# draftBoard.net
KiCad netlist of a schematic drawn in EAGLE
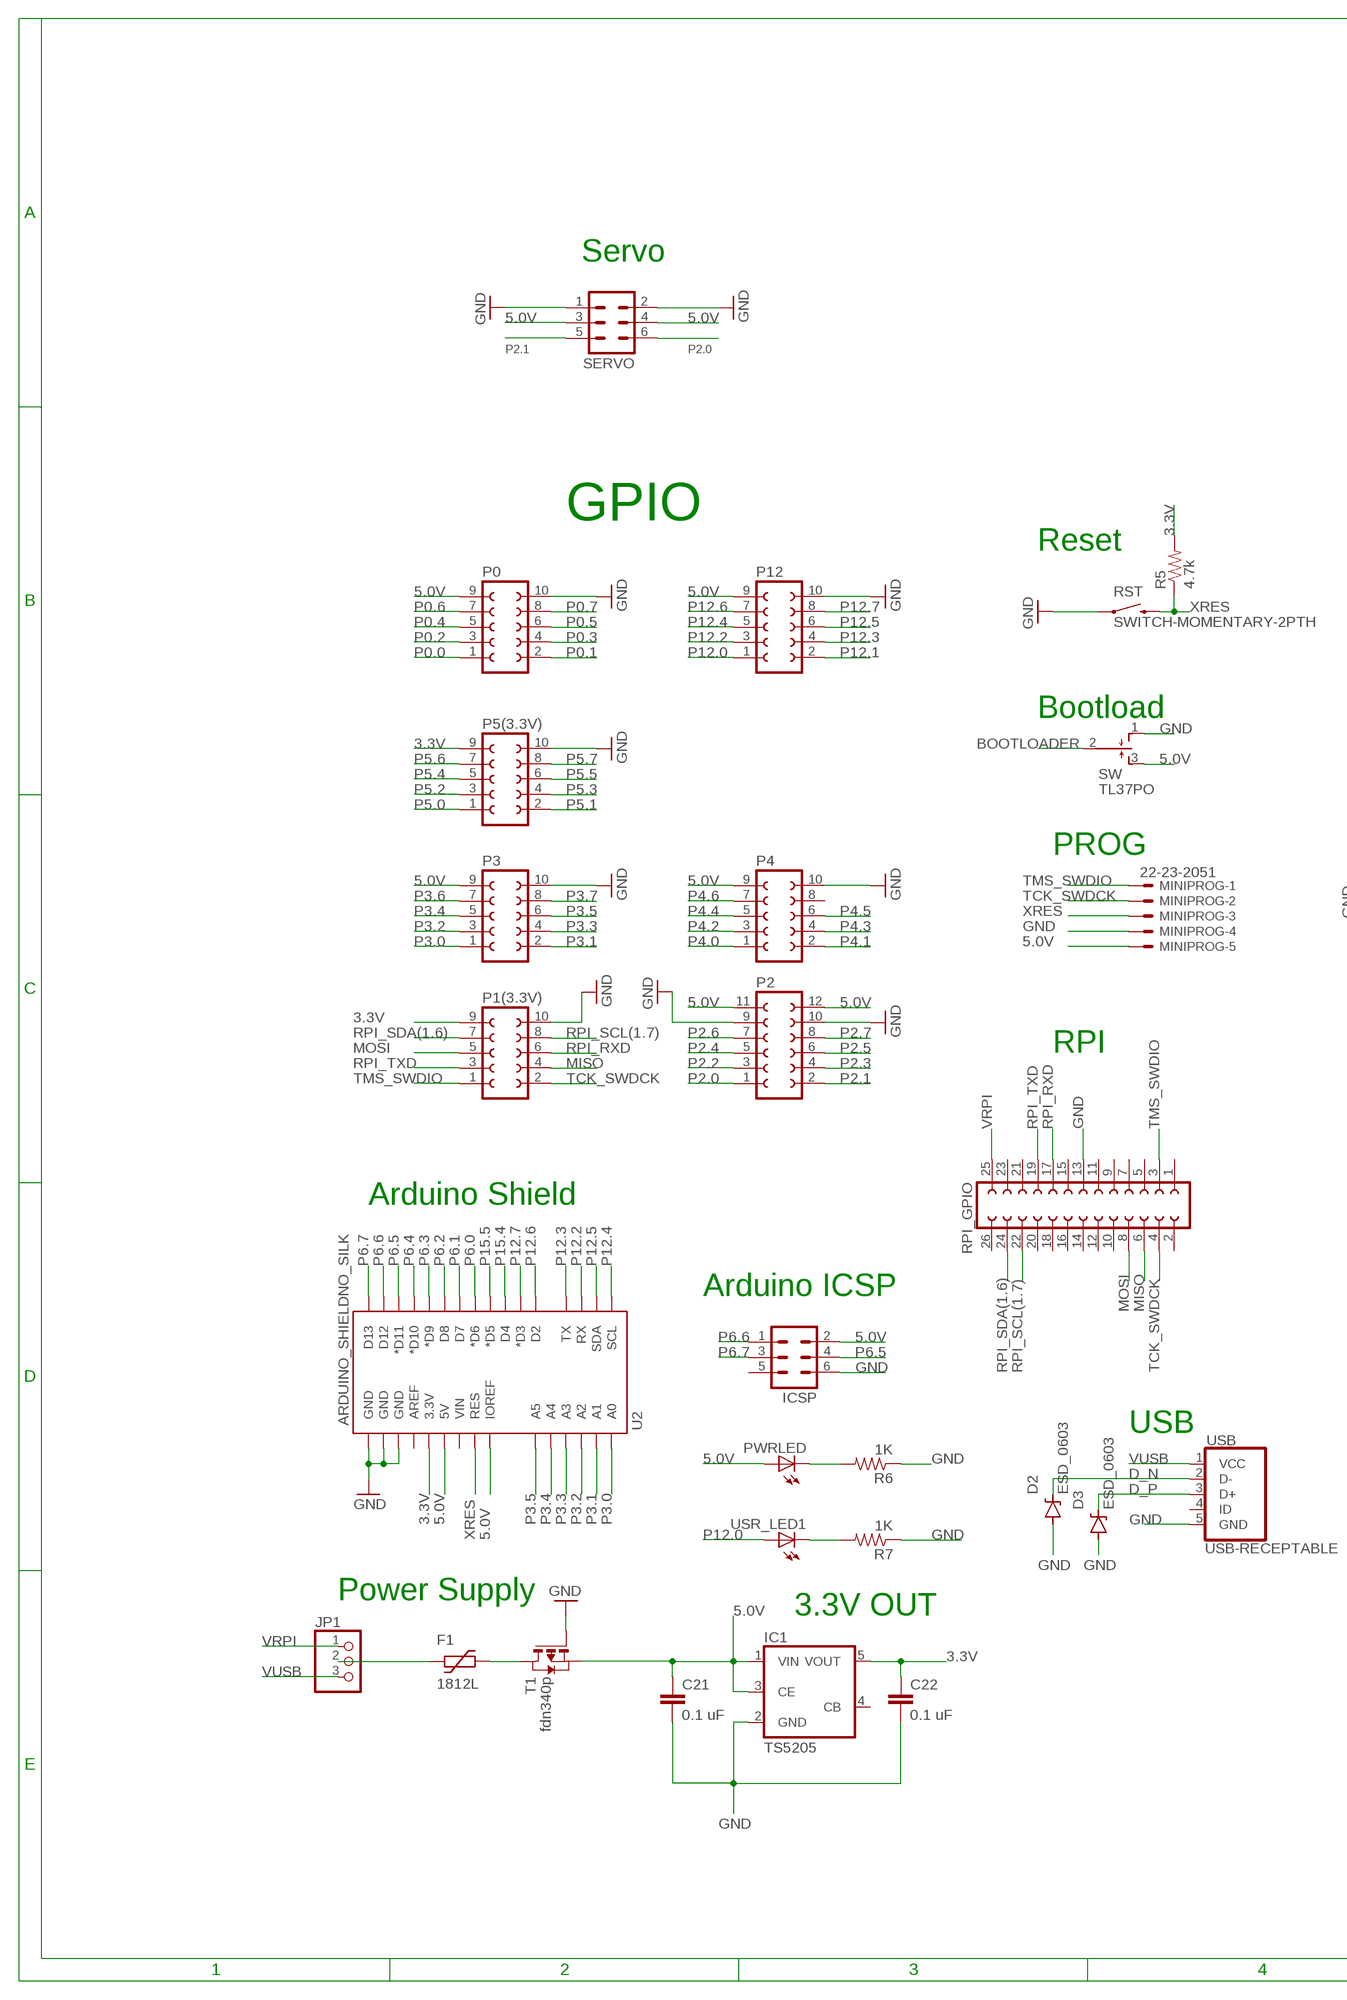
[diagram p0: schematic, sheet 1, part 1 of 2]
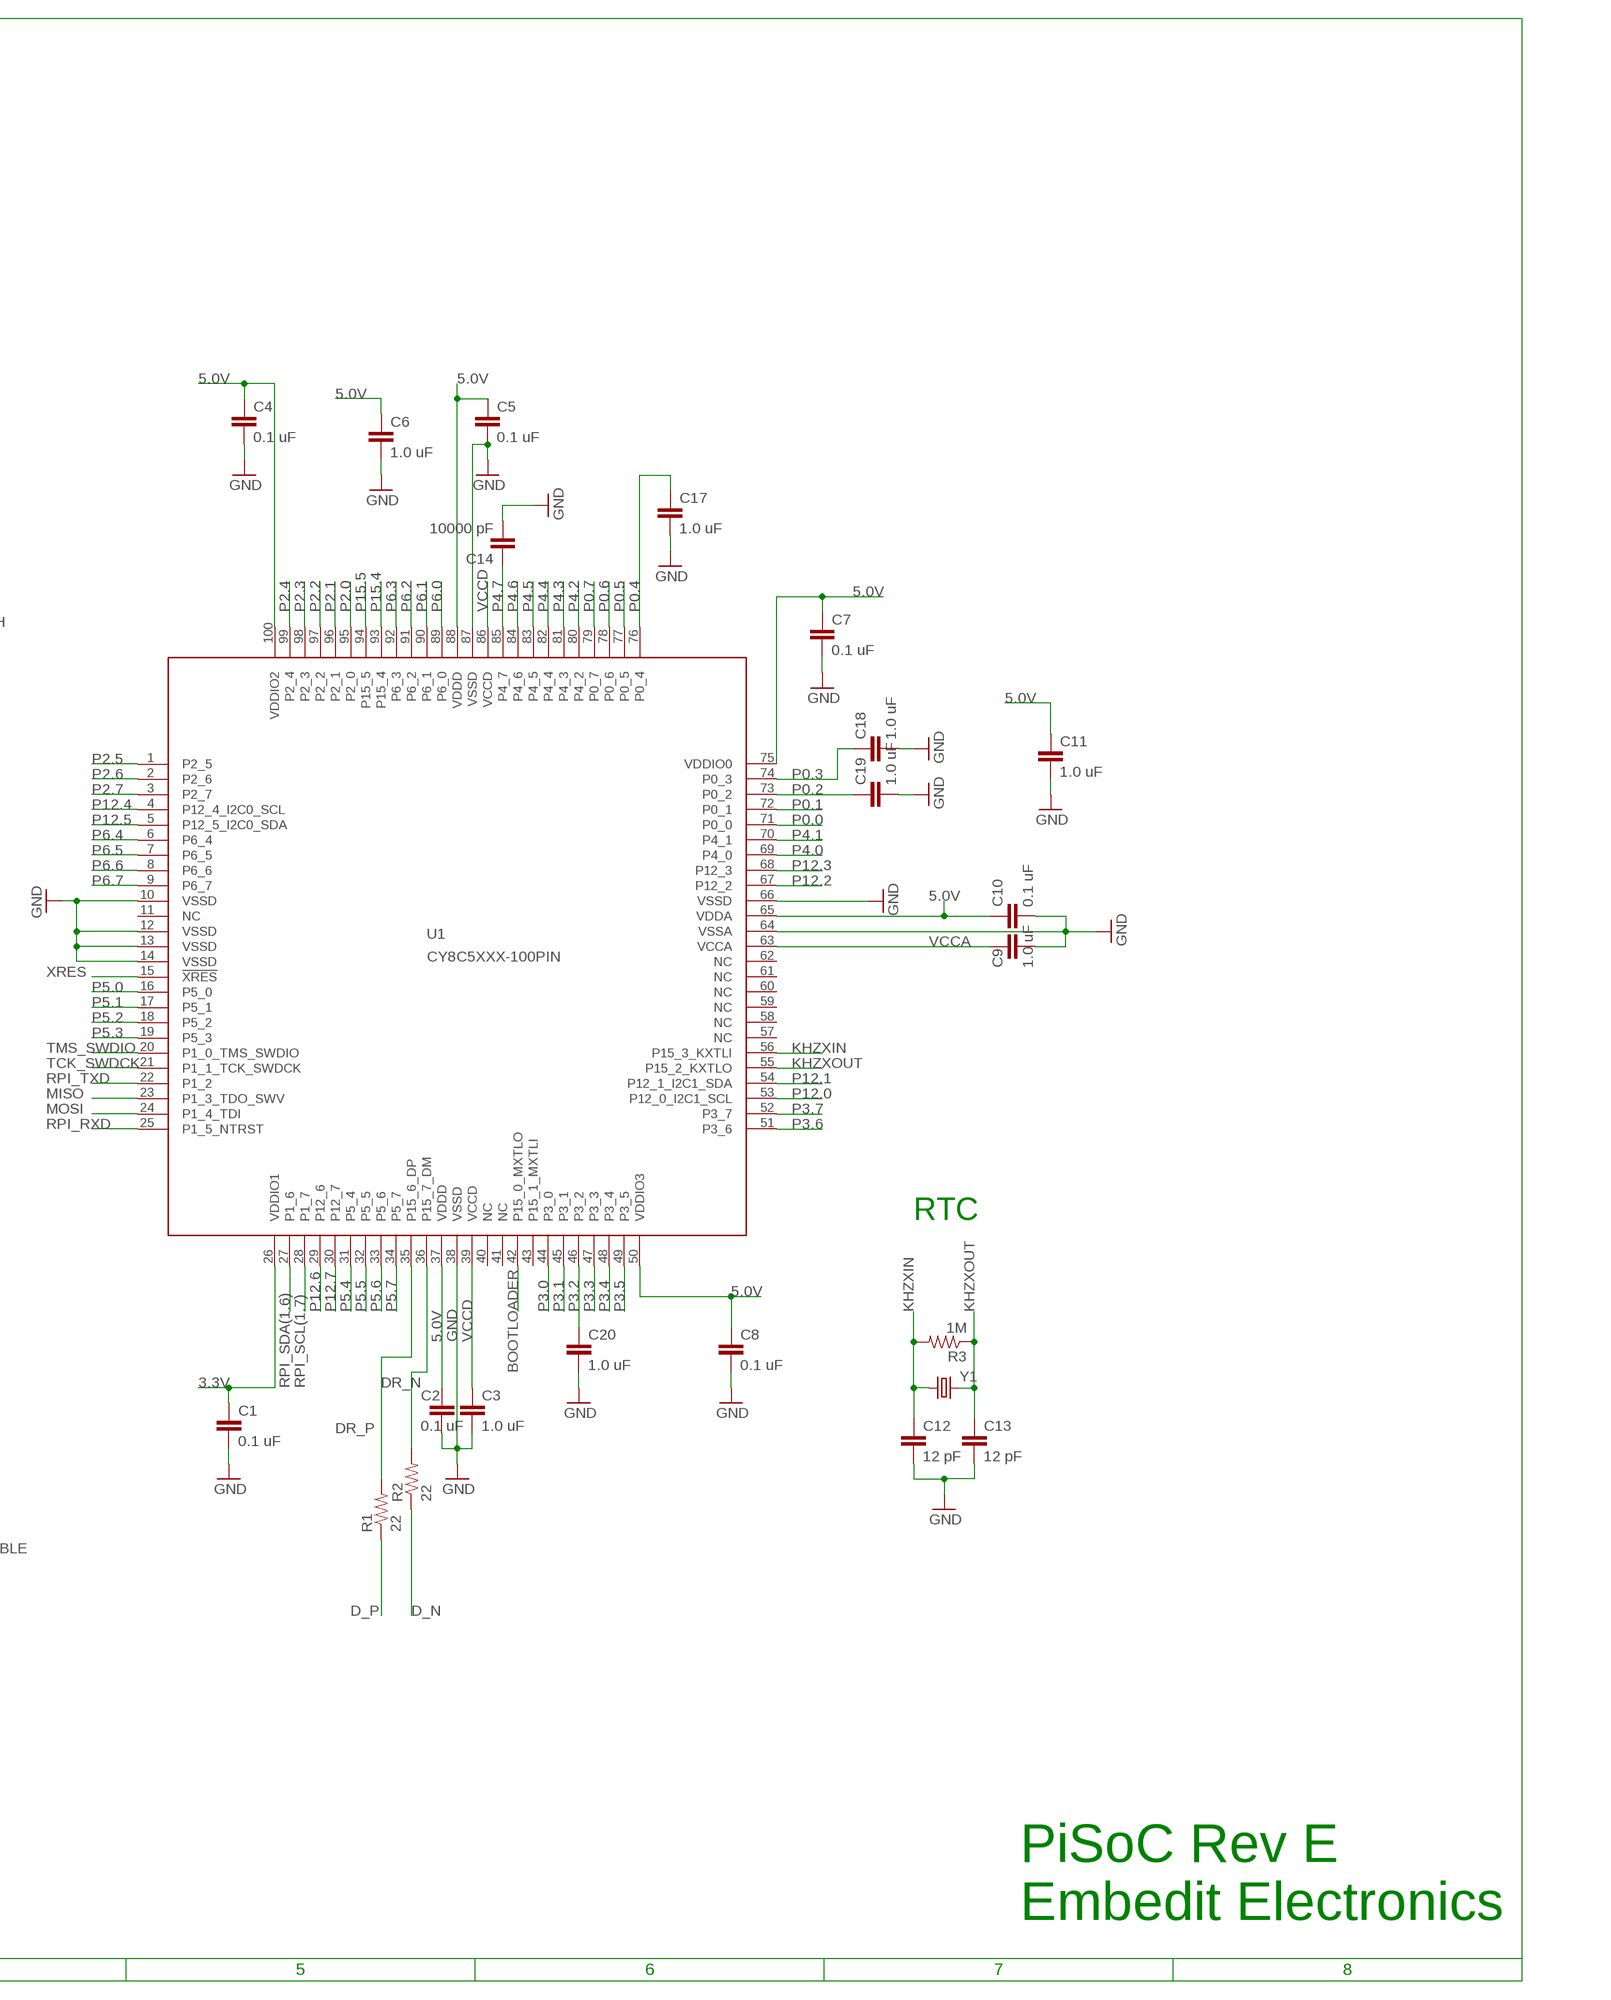
[diagram p1: schematic, sheet 1, part 2 of 2]

(export (version "E")
  (design (tool "Eeschema 10.0.6"))
  (components
    (comp (ref "C1")
      (value "0.1 uF")
      (footprint "eagle-import:0603-CAP@1")
      (libsource (lib "eagle-import") (part "CAP0603-CAP"))
    )
    (comp (ref "C2")
      (value "0.1 uF")
      (footprint "eagle-import:0603-CAP@1")
      (libsource (lib "eagle-import") (part "CAP0603-CAP"))
    )
    (comp (ref "C3")
      (value "1.0 uF")
      (footprint "eagle-import:0603-CAP@1")
      (libsource (lib "eagle-import") (part "CAP0603-CAP"))
    )
    (comp (ref "C4")
      (value "0.1 uF")
      (footprint "eagle-import:0603-CAP@1")
      (libsource (lib "eagle-import") (part "CAP0603-CAP"))
    )
    (comp (ref "C5")
      (value "0.1 uF")
      (footprint "eagle-import:0603-CAP@1")
      (libsource (lib "eagle-import") (part "CAP0603-CAP"))
    )
    (comp (ref "C6")
      (value "1.0 uF")
      (footprint "eagle-import:0603-CAP@1")
      (libsource (lib "eagle-import") (part "CAP0603-CAP"))
    )
    (comp (ref "C7")
      (value "0.1 uF")
      (footprint "eagle-import:0603-CAP@1")
      (libsource (lib "eagle-import") (part "CAP0603-CAP"))
    )
    (comp (ref "C8")
      (value "0.1 uF")
      (footprint "eagle-import:0603-CAP@1")
      (libsource (lib "eagle-import") (part "CAP0603-CAP"))
    )
    (comp (ref "C9")
      (value "1.0 uF")
      (footprint "eagle-import:0603-CAP@1")
      (libsource (lib "eagle-import") (part "CAP0603-CAP"))
    )
    (comp (ref "C10")
      (value "0.1 uF")
      (footprint "eagle-import:0603-CAP@1")
      (libsource (lib "eagle-import") (part "CAP0603-CAP"))
    )
    (comp (ref "C11")
      (value "1.0 uF")
      (footprint "eagle-import:0603-CAP@1")
      (libsource (lib "eagle-import") (part "CAP0603-CAP"))
    )
    (comp (ref "C12")
      (value "12 pF")
      (footprint "eagle-import:0603-CAP@1")
      (libsource (lib "eagle-import") (part "CAP0603-CAP"))
    )
    (comp (ref "C13")
      (value "12 pF")
      (footprint "eagle-import:0603-CAP@1")
      (libsource (lib "eagle-import") (part "CAP0603-CAP"))
    )
    (comp (ref "C14")
      (value "10000 pF")
      (footprint "eagle-import:0603-CAP@1")
      (libsource (lib "eagle-import") (part "CAP0603-CAP"))
    )
    (comp (ref "C17")
      (value "1.0 uF")
      (footprint "eagle-import:0603-CAP@1")
      (libsource (lib "eagle-import") (part "CAP0603-CAP"))
    )
    (comp (ref "C18")
      (value "1.0 uF")
      (footprint "eagle-import:0603-CAP@1")
      (libsource (lib "eagle-import") (part "CAP0603-CAP"))
    )
    (comp (ref "C19")
      (value "1.0 uF")
      (footprint "eagle-import:0603-CAP@1")
      (libsource (lib "eagle-import") (part "CAP0603-CAP"))
    )
    (comp (ref "C20")
      (value "1.0 uF")
      (footprint "eagle-import:0603-CAP@1")
      (libsource (lib "eagle-import") (part "CAP0603-CAP"))
    )
    (comp (ref "C21")
      (value "0.1 uF")
      (footprint "eagle-import:0603-CAP@1")
      (libsource (lib "eagle-import") (part "CAP0603-CAP"))
    )
    (comp (ref "C22")
      (value "0.1 uF")
      (footprint "eagle-import:0603-CAP@1")
      (libsource (lib "eagle-import") (part "CAP0603-CAP"))
    )
    (comp (ref "D2")
      (value "ESD_0603")
      (footprint "eagle-import:0603-CAP")
      (libsource (lib "eagle-import") (part "ESD_0603"))
    )
    (comp (ref "D3")
      (value "ESD_0603")
      (footprint "eagle-import:0603-CAP")
      (libsource (lib "eagle-import") (part "ESD_0603"))
    )
    (comp (ref "F1")
      (value "1812L")
      (footprint "eagle-import:1812L")
      (libsource (lib "eagle-import") (part "1812L"))
    )
    (comp (ref "IC1")
      (value "TS5205")
      (footprint "eagle-import:SOT25")
      (libsource (lib "eagle-import") (part "TS5205"))
    )
    (comp (ref "ICSP")
      (value "MA03-2")
      (footprint "eagle-import:MA03-2")
      (libsource (lib "eagle-import") (part "MA03-2"))
    )
    (comp (ref "JP1")
      (value "PINHD-1X3")
      (footprint "eagle-import:1X03")
      (libsource (lib "eagle-import") (part "PINHD-1X3"))
    )
    (comp (ref "MINIPROG")
      (value "22-23-2051")
      (footprint "eagle-import:22-23-2051")
      (fields (field (name "MF") "MOLEX"))
      (libsource (lib "eagle-import") (part "22-23-2051"))
    )
    (comp (ref "P0")
      (value "FE05-2")
      (footprint "eagle-import:FE05-2")
      (libsource (lib "eagle-import") (part "FE05-2"))
    )
    (comp (ref "P1(3.3V)")
      (value "FE05-2")
      (footprint "eagle-import:FE05-2")
      (libsource (lib "eagle-import") (part "FE05-2"))
    )
    (comp (ref "P2")
      (value "FE06-2")
      (footprint "eagle-import:FE06-2")
      (libsource (lib "eagle-import") (part "FE06-2"))
    )
    (comp (ref "P3")
      (value "FE05-2")
      (footprint "eagle-import:FE05-2")
      (libsource (lib "eagle-import") (part "FE05-2"))
    )
    (comp (ref "P4")
      (value "FE05-2")
      (footprint "eagle-import:FE05-2")
      (libsource (lib "eagle-import") (part "FE05-2"))
    )
    (comp (ref "P5(3.3V)")
      (value "FE05-2")
      (footprint "eagle-import:FE05-2")
      (libsource (lib "eagle-import") (part "FE05-2"))
    )
    (comp (ref "P12")
      (value "FE05-2")
      (footprint "eagle-import:FE05-2")
      (libsource (lib "eagle-import") (part "FE05-2"))
    )
    (comp (ref "PWRLED")
      (value "LED0603")
      (footprint "eagle-import:LED-0603")
      (libsource (lib "eagle-import") (part "LED0603"))
    )
    (comp (ref "R1")
      (value "22")
      (footprint "eagle-import:0603-RES")
      (libsource (lib "eagle-import") (part "RESISTOR0603-RES"))
    )
    (comp (ref "R2")
      (value "22")
      (footprint "eagle-import:0603-RES")
      (libsource (lib "eagle-import") (part "RESISTOR0603-RES"))
    )
    (comp (ref "R3")
      (value "1M")
      (footprint "eagle-import:0603-RES")
      (libsource (lib "eagle-import") (part "RESISTOR0603-RES"))
    )
    (comp (ref "R5")
      (value "4.7k")
      (footprint "eagle-import:0603-RES")
      (libsource (lib "eagle-import") (part "RESISTOR0603-RES"))
    )
    (comp (ref "R6")
      (value "1K")
      (footprint "eagle-import:0603-RES")
      (libsource (lib "eagle-import") (part "RESISTOR0603-RES"))
    )
    (comp (ref "R7")
      (value "1K")
      (footprint "eagle-import:0603-RES")
      (libsource (lib "eagle-import") (part "RESISTOR0603-RES"))
    )
    (comp (ref "RPI_GPIO")
      (value "FE13-2")
      (footprint "eagle-import:FE13-2")
      (libsource (lib "eagle-import") (part "FE13-2"))
    )
    (comp (ref "RST")
      (value "SWITCH-MOMENTARY-2PTH")
      (footprint "eagle-import:TACTILE-PTH")
      (libsource (lib "eagle-import") (part "SWITCH-MOMENTARY-2PTH"))
    )
    (comp (ref "SERVO")
      (value "MA03-2")
      (footprint "eagle-import:MA03-2")
      (libsource (lib "eagle-import") (part "MA03-2"))
    )
    (comp (ref "SW")
      (value "TL37PO")
      (footprint "eagle-import:TL3XPO")
      (libsource (lib "eagle-import") (part "TL37PO"))
    )
    (comp (ref "T1")
      (value "fdn340p")
      (footprint "eagle-import:SOT-23")
      (libsource (lib "eagle-import") (part "PMOSSOT23"))
    )
    (comp (ref "U1")
      (value "CY8C5XXX-100PIN")
      (footprint "eagle-import:TQFP-14X14-100")
      (fields (field (name "MPN") "CY8C5588AXI-060"))
      (libsource (lib "eagle-import") (part "CY8C5XXX-100PIN"))
    )
    (comp (ref "U2")
      (value "ARDUINO_SHIELDNO_SILK")
      (footprint "eagle-import:DUEMILANOVE_VIAS")
      (libsource (lib "eagle-import") (part "ARDUINO_SHIELDNO_SILK"))
    )
    (comp (ref "USB")
      (value "USB-RECEPTABLE")
      (footprint "eagle-import:FCI-10103594-0001LF")
      (libsource (lib "eagle-import") (part "USB-RECEPTABLE"))
    )
    (comp (ref "USR_LED1")
      (value "LED0603")
      (footprint "eagle-import:LED-0603")
      (libsource (lib "eagle-import") (part "LED0603"))
    )
    (comp (ref "Y1")
      (value "CRYSTALTC26H")
      (footprint "eagle-import:TC26H")
      (libsource (lib "eagle-import") (part "CRYSTALTC26H"))
    )
  )
  (nets
    (net (code "1") (name "/3.3V") (class "Default")
      (node (ref "C1") (pin "1") (pinfunction "1_1") (pintype "passive"))
      (node (ref "C22") (pin "1") (pinfunction "1_1") (pintype "passive"))
      (node (ref "IC1") (pin "5") (pinfunction "VOUT_5") (pintype "passive"))
      (node (ref "P1(3.3V)") (pin "9") (pinfunction "9_9") (pintype "passive"))
      (node (ref "P5(3.3V)") (pin "9") (pinfunction "9_9") (pintype "passive"))
      (node (ref "R5") (pin "2") (pinfunction "2_2") (pintype "passive"))
      (node (ref "U1") (pin "26") (pinfunction "VDDIO1_26") (pintype "passive"))
      (node (ref "U2") (pin "3.3V") (pinfunction "3.3V_3.3V") (pintype "bidirectional"))
    )
    (net (code "2") (name "/5.0V") (class "Default")
      (node (ref "C10") (pin "1") (pinfunction "1_1") (pintype "passive"))
      (node (ref "C11") (pin "1") (pinfunction "1_1") (pintype "passive"))
      (node (ref "C2") (pin "1") (pinfunction "1_1") (pintype "passive"))
      (node (ref "C21") (pin "1") (pinfunction "1_1") (pintype "passive"))
      (node (ref "C4") (pin "1") (pinfunction "1_1") (pintype "passive"))
      (node (ref "C5") (pin "1") (pinfunction "1_1") (pintype "passive"))
      (node (ref "C6") (pin "1") (pinfunction "1_1") (pintype "passive"))
      (node (ref "C7") (pin "1") (pinfunction "1_1") (pintype "passive"))
      (node (ref "C8") (pin "1") (pinfunction "1_1") (pintype "passive"))
      (node (ref "IC1") (pin "1") (pinfunction "VIN_1") (pintype "input"))
      (node (ref "IC1") (pin "3") (pinfunction "CE_3") (pintype "input"))
      (node (ref "ICSP") (pin "2") (pinfunction "2_2") (pintype "passive"))
      (node (ref "MINIPROG") (pin "5") (pinfunction "S_5") (pintype "passive"))
      (node (ref "P0") (pin "9") (pinfunction "9_9") (pintype "passive"))
      (node (ref "P12") (pin "9") (pinfunction "9_9") (pintype "passive"))
      (node (ref "P2") (pin "11") (pinfunction "11_11") (pintype "passive"))
      (node (ref "P2") (pin "12") (pinfunction "12_12") (pintype "passive"))
      (node (ref "P3") (pin "9") (pinfunction "9_9") (pintype "passive"))
      (node (ref "P4") (pin "9") (pinfunction "9_9") (pintype "passive"))
      (node (ref "PWRLED") (pin "A") (pinfunction "A_A") (pintype "passive"))
      (node (ref "SERVO") (pin "3") (pinfunction "3_3") (pintype "passive"))
      (node (ref "SERVO") (pin "4") (pinfunction "4_4") (pintype "passive"))
      (node (ref "SW") (pin "3") (pinfunction "S_3") (pintype "passive"))
      (node (ref "T1") (pin "2") (pinfunction "S_2") (pintype "passive"))
      (node (ref "U1") (pin "100") (pinfunction "VDDIO2_100") (pintype "passive"))
      (node (ref "U1") (pin "37") (pinfunction "VDDD_37") (pintype "passive"))
      (node (ref "U1") (pin "50") (pinfunction "VDDIO3_50") (pintype "passive"))
      (node (ref "U1") (pin "65") (pinfunction "VDDA_65") (pintype "passive"))
      (node (ref "U1") (pin "75") (pinfunction "VDDIO0_75") (pintype "passive"))
      (node (ref "U1") (pin "88") (pinfunction "VDDD_88") (pintype "passive"))
      (node (ref "U2") (pin "5V") (pinfunction "5V_5V") (pintype "bidirectional"))
      (node (ref "U2") (pin "IOREF") (pinfunction "IOREF_IOREF") (pintype "bidirectional"))
    )
    (net (code "3") (name "/BOOTLOADER") (class "Default")
      (node (ref "SW") (pin "2") (pinfunction "P_2") (pintype "passive"))
      (node (ref "U1") (pin "42") (pinfunction "P15_0_MXTLO_42") (pintype "passive"))
    )
    (net (code "4") (name "/DR_N") (class "Default")
      (node (ref "R2") (pin "2") (pinfunction "2_2") (pintype "passive"))
      (node (ref "U1") (pin "36") (pinfunction "P15_7_DM_36") (pintype "passive"))
    )
    (net (code "5") (name "/DR_P") (class "Default")
      (node (ref "R1") (pin "2") (pinfunction "2_2") (pintype "passive"))
      (node (ref "U1") (pin "35") (pinfunction "P15_6_DP_35") (pintype "passive"))
    )
    (net (code "6") (name "/D_N") (class "Default")
      (node (ref "D2") (pin "1") (pinfunction "C_1") (pintype "passive"))
      (node (ref "R2") (pin "1") (pinfunction "1_1") (pintype "passive"))
      (node (ref "USB") (pin "2") (pinfunction "D-_2") (pintype "bidirectional"))
    )
    (net (code "7") (name "/D_P") (class "Default")
      (node (ref "D3") (pin "1") (pinfunction "C_1") (pintype "passive"))
      (node (ref "R1") (pin "1") (pinfunction "1_1") (pintype "passive"))
      (node (ref "USB") (pin "3") (pinfunction "D+_3") (pintype "bidirectional"))
    )
    (net (code "8") (name "/KHZXIN") (class "Default")
      (node (ref "C12") (pin "1") (pinfunction "1_1") (pintype "passive"))
      (node (ref "R3") (pin "2") (pinfunction "2_2") (pintype "passive"))
      (node (ref "U1") (pin "56") (pinfunction "P15_3_KXTLI_56") (pintype "passive"))
      (node (ref "Y1") (pin "1") (pinfunction "1_1") (pintype "passive"))
    )
    (net (code "9") (name "/KHZXOUT") (class "Default")
      (node (ref "C13") (pin "1") (pinfunction "1_1") (pintype "passive"))
      (node (ref "R3") (pin "1") (pinfunction "1_1") (pintype "passive"))
      (node (ref "U1") (pin "55") (pinfunction "P15_2_KXTLO_55") (pintype "passive"))
      (node (ref "Y1") (pin "2") (pinfunction "2_2") (pintype "passive"))
    )
    (net (code "10") (name "/MISO") (class "Default")
      (node (ref "P1(3.3V)") (pin "4") (pinfunction "4_4") (pintype "passive"))
      (node (ref "RPI_GPIO") (pin "6") (pinfunction "6_6") (pintype "passive"))
      (node (ref "U1") (pin "23") (pinfunction "P1_3_TDO_SWV_23") (pintype "passive"))
    )
    (net (code "11") (name "/MOSI") (class "Default")
      (node (ref "P1(3.3V)") (pin "5") (pinfunction "5_5") (pintype "passive"))
      (node (ref "RPI_GPIO") (pin "8") (pinfunction "8_8") (pintype "passive"))
      (node (ref "U1") (pin "24") (pinfunction "P1_4_TDI_24") (pintype "passive"))
    )
    (net (code "12") (name "/P0.0") (class "Default")
      (node (ref "P0") (pin "1") (pinfunction "1_1") (pintype "passive"))
      (node (ref "U1") (pin "71") (pinfunction "P0_0_71") (pintype "passive"))
    )
    (net (code "13") (name "/P0.1") (class "Default")
      (node (ref "P0") (pin "2") (pinfunction "2_2") (pintype "passive"))
      (node (ref "U1") (pin "72") (pinfunction "P0_1_72") (pintype "passive"))
    )
    (net (code "14") (name "/P0.2") (class "Default")
      (node (ref "C19") (pin "1") (pinfunction "1_1") (pintype "passive"))
      (node (ref "P0") (pin "3") (pinfunction "3_3") (pintype "passive"))
      (node (ref "U1") (pin "73") (pinfunction "P0_2_73") (pintype "passive"))
    )
    (net (code "15") (name "/P0.3") (class "Default")
      (node (ref "C18") (pin "1") (pinfunction "1_1") (pintype "passive"))
      (node (ref "P0") (pin "4") (pinfunction "4_4") (pintype "passive"))
      (node (ref "U1") (pin "74") (pinfunction "P0_3_74") (pintype "passive"))
    )
    (net (code "16") (name "/P0.4") (class "Default")
      (node (ref "C17") (pin "1") (pinfunction "1_1") (pintype "passive"))
      (node (ref "P0") (pin "5") (pinfunction "5_5") (pintype "passive"))
      (node (ref "U1") (pin "76") (pinfunction "P0_4_76") (pintype "passive"))
    )
    (net (code "17") (name "/P0.5") (class "Default")
      (node (ref "P0") (pin "6") (pinfunction "6_6") (pintype "passive"))
      (node (ref "U1") (pin "77") (pinfunction "P0_5_77") (pintype "passive"))
    )
    (net (code "18") (name "/P0.6") (class "Default")
      (node (ref "P0") (pin "7") (pinfunction "7_7") (pintype "passive"))
      (node (ref "U1") (pin "78") (pinfunction "P0_6_78") (pintype "passive"))
    )
    (net (code "19") (name "/P0.7") (class "Default")
      (node (ref "P0") (pin "8") (pinfunction "8_8") (pintype "passive"))
      (node (ref "U1") (pin "79") (pinfunction "P0_7_79") (pintype "passive"))
    )
    (net (code "20") (name "/P2.0") (class "Default")
      (node (ref "P2") (pin "1") (pinfunction "1_1") (pintype "passive"))
      (node (ref "SERVO") (pin "6") (pinfunction "6_6") (pintype "passive"))
      (node (ref "U1") (pin "95") (pinfunction "P2_0_95") (pintype "passive"))
    )
    (net (code "21") (name "/P2.1") (class "Default")
      (node (ref "P2") (pin "2") (pinfunction "2_2") (pintype "passive"))
      (node (ref "SERVO") (pin "5") (pinfunction "5_5") (pintype "passive"))
      (node (ref "U1") (pin "96") (pinfunction "P2_1_96") (pintype "passive"))
    )
    (net (code "22") (name "/P2.2") (class "Default")
      (node (ref "P2") (pin "3") (pinfunction "3_3") (pintype "passive"))
      (node (ref "U1") (pin "97") (pinfunction "P2_2_97") (pintype "passive"))
    )
    (net (code "23") (name "/P2.3") (class "Default")
      (node (ref "P2") (pin "4") (pinfunction "4_4") (pintype "passive"))
      (node (ref "U1") (pin "98") (pinfunction "P2_3_98") (pintype "passive"))
    )
    (net (code "24") (name "/P2.4") (class "Default")
      (node (ref "P2") (pin "5") (pinfunction "5_5") (pintype "passive"))
      (node (ref "U1") (pin "99") (pinfunction "P2_4_99") (pintype "passive"))
    )
    (net (code "25") (name "/P2.5") (class "Default")
      (node (ref "P2") (pin "6") (pinfunction "6_6") (pintype "passive"))
      (node (ref "U1") (pin "1") (pinfunction "P2_5_1") (pintype "passive"))
    )
    (net (code "26") (name "/P2.6") (class "Default")
      (node (ref "P2") (pin "7") (pinfunction "7_7") (pintype "passive"))
      (node (ref "U1") (pin "2") (pinfunction "P2_6_2") (pintype "passive"))
    )
    (net (code "27") (name "/P2.7") (class "Default")
      (node (ref "P2") (pin "8") (pinfunction "8_8") (pintype "passive"))
      (node (ref "U1") (pin "3") (pinfunction "P2_7_3") (pintype "passive"))
    )
    (net (code "28") (name "/P3.0") (class "Default")
      (node (ref "P3") (pin "1") (pinfunction "1_1") (pintype "passive"))
      (node (ref "U1") (pin "44") (pinfunction "P3_0_44") (pintype "passive"))
      (node (ref "U2") (pin "A0") (pinfunction "A0_A0") (pintype "bidirectional"))
    )
    (net (code "29") (name "/P3.1") (class "Default")
      (node (ref "P3") (pin "2") (pinfunction "2_2") (pintype "passive"))
      (node (ref "U1") (pin "45") (pinfunction "P3_1_45") (pintype "passive"))
      (node (ref "U2") (pin "A1") (pinfunction "A1_A1") (pintype "bidirectional"))
    )
    (net (code "30") (name "/P3.2") (class "Default")
      (node (ref "C20") (pin "1") (pinfunction "1_1") (pintype "passive"))
      (node (ref "P3") (pin "3") (pinfunction "3_3") (pintype "passive"))
      (node (ref "U1") (pin "46") (pinfunction "P3_2_46") (pintype "passive"))
      (node (ref "U2") (pin "A2") (pinfunction "A2_A2") (pintype "bidirectional"))
    )
    (net (code "31") (name "/P3.3") (class "Default")
      (node (ref "P3") (pin "4") (pinfunction "4_4") (pintype "passive"))
      (node (ref "U1") (pin "47") (pinfunction "P3_3_47") (pintype "passive"))
      (node (ref "U2") (pin "A3") (pinfunction "A3_A3") (pintype "bidirectional"))
    )
    (net (code "32") (name "/P3.4") (class "Default")
      (node (ref "P3") (pin "5") (pinfunction "5_5") (pintype "passive"))
      (node (ref "U1") (pin "48") (pinfunction "P3_4_48") (pintype "passive"))
      (node (ref "U2") (pin "A4") (pinfunction "A4_A4") (pintype "bidirectional"))
    )
    (net (code "33") (name "/P3.5") (class "Default")
      (node (ref "P3") (pin "6") (pinfunction "6_6") (pintype "passive"))
      (node (ref "U1") (pin "49") (pinfunction "P3_5_49") (pintype "passive"))
      (node (ref "U2") (pin "A5") (pinfunction "A5_A5") (pintype "bidirectional"))
    )
    (net (code "34") (name "/P3.6") (class "Default")
      (node (ref "P3") (pin "7") (pinfunction "7_7") (pintype "passive"))
      (node (ref "U1") (pin "51") (pinfunction "P3_6_51") (pintype "passive"))
    )
    (net (code "35") (name "/P3.7") (class "Default")
      (node (ref "P3") (pin "8") (pinfunction "8_8") (pintype "passive"))
      (node (ref "U1") (pin "52") (pinfunction "P3_7_52") (pintype "passive"))
    )
    (net (code "36") (name "/P4.0") (class "Default")
      (node (ref "P4") (pin "1") (pinfunction "1_1") (pintype "passive"))
      (node (ref "U1") (pin "69") (pinfunction "P4_0_69") (pintype "passive"))
    )
    (net (code "37") (name "/P4.1") (class "Default")
      (node (ref "P4") (pin "2") (pinfunction "2_2") (pintype "passive"))
      (node (ref "U1") (pin "70") (pinfunction "P4_1_70") (pintype "passive"))
    )
    (net (code "38") (name "/P4.2") (class "Default")
      (node (ref "P4") (pin "3") (pinfunction "3_3") (pintype "passive"))
      (node (ref "U1") (pin "80") (pinfunction "P4_2_80") (pintype "passive"))
    )
    (net (code "39") (name "/P4.3") (class "Default")
      (node (ref "P4") (pin "4") (pinfunction "4_4") (pintype "passive"))
      (node (ref "U1") (pin "81") (pinfunction "P4_3_81") (pintype "passive"))
    )
    (net (code "40") (name "/P4.4") (class "Default")
      (node (ref "P4") (pin "5") (pinfunction "5_5") (pintype "passive"))
      (node (ref "U1") (pin "82") (pinfunction "P4_4_82") (pintype "passive"))
    )
    (net (code "41") (name "/P4.5") (class "Default")
      (node (ref "P4") (pin "6") (pinfunction "6_6") (pintype "passive"))
      (node (ref "U1") (pin "83") (pinfunction "P4_5_83") (pintype "passive"))
    )
    (net (code "42") (name "/P4.6") (class "Default")
      (node (ref "P4") (pin "7") (pinfunction "7_7") (pintype "passive"))
      (node (ref "U1") (pin "84") (pinfunction "P4_6_84") (pintype "passive"))
    )
    (net (code "43") (name "/P4.7") (class "Default")
      (node (ref "C14") (pin "1") (pinfunction "1_1") (pintype "passive"))
      (node (ref "U1") (pin "85") (pinfunction "P4_7_85") (pintype "passive"))
    )
    (net (code "44") (name "/P5.0") (class "Default")
      (node (ref "P5(3.3V)") (pin "1") (pinfunction "1_1") (pintype "passive"))
      (node (ref "U1") (pin "16") (pinfunction "P5_0_16") (pintype "passive"))
    )
    (net (code "45") (name "/P5.1") (class "Default")
      (node (ref "P5(3.3V)") (pin "2") (pinfunction "2_2") (pintype "passive"))
      (node (ref "U1") (pin "17") (pinfunction "P5_1_17") (pintype "passive"))
    )
    (net (code "46") (name "/P5.2") (class "Default")
      (node (ref "P5(3.3V)") (pin "3") (pinfunction "3_3") (pintype "passive"))
      (node (ref "U1") (pin "18") (pinfunction "P5_2_18") (pintype "passive"))
    )
    (net (code "47") (name "/P5.3") (class "Default")
      (node (ref "P5(3.3V)") (pin "4") (pinfunction "4_4") (pintype "passive"))
      (node (ref "U1") (pin "19") (pinfunction "P5_3_19") (pintype "passive"))
    )
    (net (code "48") (name "/P5.4") (class "Default")
      (node (ref "P5(3.3V)") (pin "5") (pinfunction "5_5") (pintype "passive"))
      (node (ref "U1") (pin "31") (pinfunction "P5_4_31") (pintype "passive"))
    )
    (net (code "49") (name "/P5.5") (class "Default")
      (node (ref "P5(3.3V)") (pin "6") (pinfunction "6_6") (pintype "passive"))
      (node (ref "U1") (pin "32") (pinfunction "P5_5_32") (pintype "passive"))
    )
    (net (code "50") (name "/P5.6") (class "Default")
      (node (ref "P5(3.3V)") (pin "7") (pinfunction "7_7") (pintype "passive"))
      (node (ref "U1") (pin "33") (pinfunction "P5_6_33") (pintype "passive"))
    )
    (net (code "51") (name "/P5.7") (class "Default")
      (node (ref "P5(3.3V)") (pin "8") (pinfunction "8_8") (pintype "passive"))
      (node (ref "U1") (pin "34") (pinfunction "P5_7_34") (pintype "passive"))
    )
    (net (code "52") (name "/P6.0") (class "Default")
      (node (ref "U1") (pin "89") (pinfunction "P6_0_89") (pintype "passive"))
      (node (ref "U2") (pin "D6") (pinfunction "*D6_D6") (pintype "bidirectional"))
    )
    (net (code "53") (name "/P6.1") (class "Default")
      (node (ref "U1") (pin "90") (pinfunction "P6_1_90") (pintype "passive"))
      (node (ref "U2") (pin "D7") (pinfunction "D7_D7") (pintype "bidirectional"))
    )
    (net (code "54") (name "/P6.2") (class "Default")
      (node (ref "U1") (pin "91") (pinfunction "P6_2_91") (pintype "passive"))
      (node (ref "U2") (pin "D8") (pinfunction "D8_D8") (pintype "bidirectional"))
    )
    (net (code "55") (name "/P6.3") (class "Default")
      (node (ref "U1") (pin "92") (pinfunction "P6_3_92") (pintype "passive"))
      (node (ref "U2") (pin "D9") (pinfunction "*D9_D9") (pintype "bidirectional"))
    )
    (net (code "56") (name "/P6.4") (class "Default")
      (node (ref "U1") (pin "6") (pinfunction "P6_4_6") (pintype "passive"))
      (node (ref "U2") (pin "D10") (pinfunction "*D10_D10") (pintype "bidirectional"))
    )
    (net (code "57") (name "/P6.5") (class "Default")
      (node (ref "ICSP") (pin "4") (pinfunction "4_4") (pintype "passive"))
      (node (ref "U1") (pin "7") (pinfunction "P6_5_7") (pintype "passive"))
      (node (ref "U2") (pin "D11") (pinfunction "*D11_D11") (pintype "bidirectional"))
    )
    (net (code "58") (name "/P6.6") (class "Default")
      (node (ref "ICSP") (pin "1") (pinfunction "1_1") (pintype "passive"))
      (node (ref "U1") (pin "8") (pinfunction "P6_6_8") (pintype "passive"))
      (node (ref "U2") (pin "D12") (pinfunction "D12_D12") (pintype "bidirectional"))
    )
    (net (code "59") (name "/P6.7") (class "Default")
      (node (ref "ICSP") (pin "3") (pinfunction "3_3") (pintype "passive"))
      (node (ref "U1") (pin "9") (pinfunction "P6_7_9") (pintype "passive"))
      (node (ref "U2") (pin "D13") (pinfunction "D13_D13") (pintype "bidirectional"))
    )
    (net (code "60") (name "/P12.0") (class "Default")
      (node (ref "P12") (pin "1") (pinfunction "1_1") (pintype "passive"))
      (node (ref "U1") (pin "53") (pinfunction "P12_0_I2C1_SCL_53") (pintype "passive"))
      (node (ref "USR_LED1") (pin "A") (pinfunction "A_A") (pintype "passive"))
    )
    (net (code "61") (name "/P12.1") (class "Default")
      (node (ref "P12") (pin "2") (pinfunction "2_2") (pintype "passive"))
      (node (ref "U1") (pin "54") (pinfunction "P12_1_I2C1_SDA_54") (pintype "passive"))
    )
    (net (code "62") (name "/P12.2") (class "Default")
      (node (ref "P12") (pin "3") (pinfunction "3_3") (pintype "passive"))
      (node (ref "U1") (pin "67") (pinfunction "P12_2_67") (pintype "passive"))
      (node (ref "U2") (pin "RX") (pinfunction "RX_RX") (pintype "bidirectional"))
    )
    (net (code "63") (name "/P12.3") (class "Default")
      (node (ref "P12") (pin "4") (pinfunction "4_4") (pintype "passive"))
      (node (ref "U1") (pin "68") (pinfunction "P12_3_68") (pintype "passive"))
      (node (ref "U2") (pin "TX") (pinfunction "TX_TX") (pintype "bidirectional"))
    )
    (net (code "64") (name "/P12.4") (class "Default")
      (node (ref "P12") (pin "5") (pinfunction "5_5") (pintype "passive"))
      (node (ref "U1") (pin "4") (pinfunction "P12_4_I2C0_SCL_4") (pintype "passive"))
      (node (ref "U2") (pin "SCL") (pinfunction "SCL_SCL") (pintype "bidirectional"))
    )
    (net (code "65") (name "/P12.5") (class "Default")
      (node (ref "P12") (pin "6") (pinfunction "6_6") (pintype "passive"))
      (node (ref "U1") (pin "5") (pinfunction "P12_5_I2C0_SDA_5") (pintype "passive"))
      (node (ref "U2") (pin "SDA") (pinfunction "SDA_SDA") (pintype "bidirectional"))
    )
    (net (code "66") (name "/P12.6") (class "Default")
      (node (ref "P12") (pin "7") (pinfunction "7_7") (pintype "passive"))
      (node (ref "U1") (pin "29") (pinfunction "P12_6_29") (pintype "passive"))
      (node (ref "U2") (pin "D2") (pinfunction "D2_D2") (pintype "bidirectional"))
    )
    (net (code "67") (name "/P12.7") (class "Default")
      (node (ref "P12") (pin "8") (pinfunction "8_8") (pintype "passive"))
      (node (ref "U1") (pin "30") (pinfunction "P12_7_30") (pintype "passive"))
      (node (ref "U2") (pin "D3") (pinfunction "*D3_D3") (pintype "bidirectional"))
    )
    (net (code "68") (name "/P15.4") (class "Default")
      (node (ref "U1") (pin "93") (pinfunction "P15_4_93") (pintype "passive"))
      (node (ref "U2") (pin "D4") (pinfunction "D4_D4") (pintype "bidirectional"))
    )
    (net (code "69") (name "/P15.5") (class "Default")
      (node (ref "U1") (pin "94") (pinfunction "P15_5_94") (pintype "passive"))
      (node (ref "U2") (pin "D5") (pinfunction "*D5_D5") (pintype "bidirectional"))
    )
    (net (code "70") (name "/RPI_RXD") (class "Default")
      (node (ref "P1(3.3V)") (pin "6") (pinfunction "6_6") (pintype "passive"))
      (node (ref "RPI_GPIO") (pin "17") (pinfunction "17_17") (pintype "passive"))
      (node (ref "U1") (pin "25") (pinfunction "P1_5_NTRST_25") (pintype "passive"))
    )
    (net (code "71") (name "/RPI_SCL(1.7)") (class "Default")
      (node (ref "P1(3.3V)") (pin "8") (pinfunction "8_8") (pintype "passive"))
      (node (ref "RPI_GPIO") (pin "22") (pinfunction "22_22") (pintype "passive"))
      (node (ref "U1") (pin "28") (pinfunction "P1_7_28") (pintype "passive"))
    )
    (net (code "72") (name "/RPI_SDA(1.6)") (class "Default")
      (node (ref "P1(3.3V)") (pin "7") (pinfunction "7_7") (pintype "passive"))
      (node (ref "RPI_GPIO") (pin "24") (pinfunction "24_24") (pintype "passive"))
      (node (ref "U1") (pin "27") (pinfunction "P1_6_27") (pintype "passive"))
    )
    (net (code "73") (name "/RPI_TXD") (class "Default")
      (node (ref "P1(3.3V)") (pin "3") (pinfunction "3_3") (pintype "passive"))
      (node (ref "RPI_GPIO") (pin "19") (pinfunction "19_19") (pintype "passive"))
      (node (ref "U1") (pin "22") (pinfunction "P1_2_22") (pintype "passive"))
    )
    (net (code "74") (name "/TCK_SWDCK") (class "Default")
      (node (ref "MINIPROG") (pin "2") (pinfunction "S_2") (pintype "passive"))
      (node (ref "P1(3.3V)") (pin "2") (pinfunction "2_2") (pintype "passive"))
      (node (ref "RPI_GPIO") (pin "4") (pinfunction "4_4") (pintype "passive"))
      (node (ref "U1") (pin "21") (pinfunction "P1_1_TCK_SWDCK_21") (pintype "passive"))
    )
    (net (code "75") (name "/TMS_SWDIO") (class "Default")
      (node (ref "MINIPROG") (pin "1") (pinfunction "S_1") (pintype "passive"))
      (node (ref "P1(3.3V)") (pin "1") (pinfunction "1_1") (pintype "passive"))
      (node (ref "RPI_GPIO") (pin "3") (pinfunction "3_3") (pintype "passive"))
      (node (ref "U1") (pin "20") (pinfunction "P1_0_TMS_SWDIO_20") (pintype "passive"))
    )
    (net (code "76") (name "/VCCA") (class "Default")
      (node (ref "C9") (pin "1") (pinfunction "1_1") (pintype "passive"))
      (node (ref "U1") (pin "63") (pinfunction "VCCA_63") (pintype "passive"))
    )
    (net (code "77") (name "/VCCD") (class "Default")
      (node (ref "C3") (pin "1") (pinfunction "1_1") (pintype "passive"))
      (node (ref "U1") (pin "39") (pinfunction "VCCD_39") (pintype "passive"))
      (node (ref "U1") (pin "86") (pinfunction "VCCD_86") (pintype "passive"))
    )
    (net (code "78") (name "/VRPI") (class "Default")
      (node (ref "JP1") (pin "1") (pinfunction "1_1") (pintype "passive"))
      (node (ref "RPI_GPIO") (pin "25") (pinfunction "25_25") (pintype "passive"))
    )
    (net (code "79") (name "/VUSB") (class "Default")
      (node (ref "JP1") (pin "3") (pinfunction "3_3") (pintype "passive"))
      (node (ref "USB") (pin "1") (pinfunction "VCC_1") (pintype "bidirectional"))
    )
    (net (code "80") (name "/XRES") (class "Default")
      (node (ref "MINIPROG") (pin "3") (pinfunction "S_3") (pintype "passive"))
      (node (ref "R5") (pin "1") (pinfunction "1_1") (pintype "passive"))
      (node (ref "RST") (pin "3") (pinfunction "2_3") (pintype "passive"))
      (node (ref "U1") (pin "15") (pinfunction "~{XRES}_15") (pintype "passive"))
      (node (ref "U2") (pin "RES") (pinfunction "RES_RES") (pintype "bidirectional"))
    )
    (net (code "81") (name "GND") (class "Default")
      (node (ref "C1") (pin "2") (pinfunction "2_2") (pintype "passive"))
      (node (ref "C10") (pin "2") (pinfunction "2_2") (pintype "passive"))
      (node (ref "C11") (pin "2") (pinfunction "2_2") (pintype "passive"))
      (node (ref "C12") (pin "2") (pinfunction "2_2") (pintype "passive"))
      (node (ref "C13") (pin "2") (pinfunction "2_2") (pintype "passive"))
      (node (ref "C14") (pin "2") (pinfunction "2_2") (pintype "passive"))
      (node (ref "C17") (pin "2") (pinfunction "2_2") (pintype "passive"))
      (node (ref "C18") (pin "2") (pinfunction "2_2") (pintype "passive"))
      (node (ref "C19") (pin "2") (pinfunction "2_2") (pintype "passive"))
      (node (ref "C2") (pin "2") (pinfunction "2_2") (pintype "passive"))
      (node (ref "C20") (pin "2") (pinfunction "2_2") (pintype "passive"))
      (node (ref "C21") (pin "2") (pinfunction "2_2") (pintype "passive"))
      (node (ref "C22") (pin "2") (pinfunction "2_2") (pintype "passive"))
      (node (ref "C3") (pin "2") (pinfunction "2_2") (pintype "passive"))
      (node (ref "C4") (pin "2") (pinfunction "2_2") (pintype "passive"))
      (node (ref "C5") (pin "2") (pinfunction "2_2") (pintype "passive"))
      (node (ref "C6") (pin "2") (pinfunction "2_2") (pintype "passive"))
      (node (ref "C7") (pin "2") (pinfunction "2_2") (pintype "passive"))
      (node (ref "C8") (pin "2") (pinfunction "2_2") (pintype "passive"))
      (node (ref "C9") (pin "2") (pinfunction "2_2") (pintype "passive"))
      (node (ref "D2") (pin "2") (pinfunction "A_2") (pintype "passive"))
      (node (ref "D3") (pin "2") (pinfunction "A_2") (pintype "passive"))
      (node (ref "IC1") (pin "2") (pinfunction "GND_2") (pintype "passive"))
      (node (ref "ICSP") (pin "6") (pinfunction "6_6") (pintype "passive"))
      (node (ref "MINIPROG") (pin "4") (pinfunction "S_4") (pintype "passive"))
      (node (ref "P0") (pin "10") (pinfunction "10_10") (pintype "passive"))
      (node (ref "P1(3.3V)") (pin "10") (pinfunction "10_10") (pintype "passive"))
      (node (ref "P12") (pin "10") (pinfunction "10_10") (pintype "passive"))
      (node (ref "P2") (pin "10") (pinfunction "10_10") (pintype "passive"))
      (node (ref "P2") (pin "9") (pinfunction "9_9") (pintype "passive"))
      (node (ref "P3") (pin "10") (pinfunction "10_10") (pintype "passive"))
      (node (ref "P4") (pin "10") (pinfunction "10_10") (pintype "passive"))
      (node (ref "P5(3.3V)") (pin "10") (pinfunction "10_10") (pintype "passive"))
      (node (ref "R6") (pin "1") (pinfunction "1_1") (pintype "passive"))
      (node (ref "R7") (pin "1") (pinfunction "1_1") (pintype "passive"))
      (node (ref "RPI_GPIO") (pin "13") (pinfunction "13_13") (pintype "passive"))
      (node (ref "RST") (pin "1") (pinfunction "1_1") (pintype "passive"))
      (node (ref "SERVO") (pin "1") (pinfunction "1_1") (pintype "passive"))
      (node (ref "SERVO") (pin "2") (pinfunction "2_2") (pintype "passive"))
      (node (ref "SW") (pin "1") (pinfunction "O_1") (pintype "passive"))
      (node (ref "T1") (pin "3") (pinfunction "G_3") (pintype "passive"))
      (node (ref "U1") (pin "10") (pinfunction "VSSD_10") (pintype "passive"))
      (node (ref "U1") (pin "12") (pinfunction "VSSD_12") (pintype "passive"))
      (node (ref "U1") (pin "13") (pinfunction "VSSD_13") (pintype "passive"))
      (node (ref "U1") (pin "14") (pinfunction "VSSD_14") (pintype "passive"))
      (node (ref "U1") (pin "38") (pinfunction "VSSD_38") (pintype "passive"))
      (node (ref "U1") (pin "64") (pinfunction "VSSA_64") (pintype "passive"))
      (node (ref "U1") (pin "66") (pinfunction "VSSD_66") (pintype "passive"))
      (node (ref "U1") (pin "87") (pinfunction "VSSD_87") (pintype "passive"))
      (node (ref "U2") (pin "GND@0") (pinfunction "GND_GND@0") (pintype "bidirectional"))
      (node (ref "U2") (pin "GND@1") (pinfunction "GND_GND@1") (pintype "bidirectional"))
      (node (ref "U2") (pin "GND@2") (pinfunction "GND_GND@2") (pintype "bidirectional"))
      (node (ref "USB") (pin "5") (pinfunction "GND_5") (pintype "bidirectional"))
    )
    (net (code "82") (name "Net-(F1-1)") (class "Default")
      (node (ref "F1") (pin "P$1") (pinfunction "1_P$1") (pintype "passive"))
      (node (ref "JP1") (pin "2") (pinfunction "2_2") (pintype "passive"))
    )
    (net (code "83") (name "Net-(F1-2)") (class "Default")
      (node (ref "F1") (pin "P$2") (pinfunction "2_P$2") (pintype "passive"))
      (node (ref "T1") (pin "1") (pinfunction "D_1") (pintype "passive"))
    )
    (net (code "84") (name "Net-(PWRLED-PadC)") (class "Default")
      (node (ref "PWRLED") (pin "C") (pinfunction "C_C") (pintype "passive"))
      (node (ref "R6") (pin "2") (pinfunction "2_2") (pintype "passive"))
    )
    (net (code "85") (name "Net-(R7-Pad2)") (class "Default")
      (node (ref "R7") (pin "2") (pinfunction "2_2") (pintype "passive"))
      (node (ref "USR_LED1") (pin "C") (pinfunction "C_C") (pintype "passive"))
    )
    (net (code "86") (name "unconnected-(IC1-CB-Pad4)") (class "Default")
      (node (ref "IC1") (pin "4") (pinfunction "CB_4") (pintype "input"))
    )
    (net (code "87") (name "unconnected-(ICSP-Pad5)") (class "Default")
      (node (ref "ICSP") (pin "5") (pinfunction "5_5") (pintype "passive"))
    )
    (net (code "88") (name "unconnected-(P4-Pad8)") (class "Default")
      (node (ref "P4") (pin "8") (pinfunction "8_8") (pintype "passive"))
    )
    (net (code "89") (name "unconnected-(RPI_GPIO-Pad1)") (class "Default")
      (node (ref "RPI_GPIO") (pin "1") (pinfunction "1_1") (pintype "passive"))
    )
    (net (code "90") (name "unconnected-(RPI_GPIO-Pad2)") (class "Default")
      (node (ref "RPI_GPIO") (pin "2") (pinfunction "2_2") (pintype "passive"))
    )
    (net (code "91") (name "unconnected-(RPI_GPIO-Pad5)") (class "Default")
      (node (ref "RPI_GPIO") (pin "5") (pinfunction "5_5") (pintype "passive"))
    )
    (net (code "92") (name "unconnected-(RPI_GPIO-Pad7)") (class "Default")
      (node (ref "RPI_GPIO") (pin "7") (pinfunction "7_7") (pintype "passive"))
    )
    (net (code "93") (name "unconnected-(RPI_GPIO-Pad9)") (class "Default")
      (node (ref "RPI_GPIO") (pin "9") (pinfunction "9_9") (pintype "passive"))
    )
    (net (code "94") (name "unconnected-(RPI_GPIO-Pad10)") (class "Default")
      (node (ref "RPI_GPIO") (pin "10") (pinfunction "10_10") (pintype "passive"))
    )
    (net (code "95") (name "unconnected-(RPI_GPIO-Pad11)") (class "Default")
      (node (ref "RPI_GPIO") (pin "11") (pinfunction "11_11") (pintype "passive"))
    )
    (net (code "96") (name "unconnected-(RPI_GPIO-Pad12)") (class "Default")
      (node (ref "RPI_GPIO") (pin "12") (pinfunction "12_12") (pintype "passive"))
    )
    (net (code "97") (name "unconnected-(RPI_GPIO-Pad14)") (class "Default")
      (node (ref "RPI_GPIO") (pin "14") (pinfunction "14_14") (pintype "passive"))
    )
    (net (code "98") (name "unconnected-(RPI_GPIO-Pad15)") (class "Default")
      (node (ref "RPI_GPIO") (pin "15") (pinfunction "15_15") (pintype "passive"))
    )
    (net (code "99") (name "unconnected-(RPI_GPIO-Pad16)") (class "Default")
      (node (ref "RPI_GPIO") (pin "16") (pinfunction "16_16") (pintype "passive"))
    )
    (net (code "100") (name "unconnected-(RPI_GPIO-Pad18)") (class "Default")
      (node (ref "RPI_GPIO") (pin "18") (pinfunction "18_18") (pintype "passive"))
    )
    (net (code "101") (name "unconnected-(RPI_GPIO-Pad20)") (class "Default")
      (node (ref "RPI_GPIO") (pin "20") (pinfunction "20_20") (pintype "passive"))
    )
    (net (code "102") (name "unconnected-(RPI_GPIO-Pad21)") (class "Default")
      (node (ref "RPI_GPIO") (pin "21") (pinfunction "21_21") (pintype "passive"))
    )
    (net (code "103") (name "unconnected-(RPI_GPIO-Pad23)") (class "Default")
      (node (ref "RPI_GPIO") (pin "23") (pinfunction "23_23") (pintype "passive"))
    )
    (net (code "104") (name "unconnected-(RPI_GPIO-Pad26)") (class "Default")
      (node (ref "RPI_GPIO") (pin "26") (pinfunction "26_26") (pintype "passive"))
    )
    (net (code "105") (name "unconnected-(U1-NC-Pad11)") (class "Default")
      (node (ref "U1") (pin "11") (pinfunction "NC_11") (pintype "passive"))
    )
    (net (code "106") (name "unconnected-(U1-NC-Pad40)") (class "Default")
      (node (ref "U1") (pin "40") (pinfunction "NC_40") (pintype "passive"))
    )
    (net (code "107") (name "unconnected-(U1-NC-Pad41)") (class "Default")
      (node (ref "U1") (pin "41") (pinfunction "NC_41") (pintype "passive"))
    )
    (net (code "108") (name "unconnected-(U1-NC-Pad57)") (class "Default")
      (node (ref "U1") (pin "57") (pinfunction "NC_57") (pintype "passive"))
    )
    (net (code "109") (name "unconnected-(U1-NC-Pad58)") (class "Default")
      (node (ref "U1") (pin "58") (pinfunction "NC_58") (pintype "passive"))
    )
    (net (code "110") (name "unconnected-(U1-NC-Pad59)") (class "Default")
      (node (ref "U1") (pin "59") (pinfunction "NC_59") (pintype "passive"))
    )
    (net (code "111") (name "unconnected-(U1-NC-Pad60)") (class "Default")
      (node (ref "U1") (pin "60") (pinfunction "NC_60") (pintype "passive"))
    )
    (net (code "112") (name "unconnected-(U1-NC-Pad61)") (class "Default")
      (node (ref "U1") (pin "61") (pinfunction "NC_61") (pintype "passive"))
    )
    (net (code "113") (name "unconnected-(U1-NC-Pad62)") (class "Default")
      (node (ref "U1") (pin "62") (pinfunction "NC_62") (pintype "passive"))
    )
    (net (code "114") (name "unconnected-(U1-P15_1_MXTLI-Pad43)") (class "Default")
      (node (ref "U1") (pin "43") (pinfunction "P15_1_MXTLI_43") (pintype "passive"))
    )
    (net (code "115") (name "unconnected-(U2-PadAREF)") (class "Default")
      (node (ref "U2") (pin "AREF") (pinfunction "AREF_AREF") (pintype "bidirectional"))
    )
    (net (code "116") (name "unconnected-(U2-PadVIN)") (class "Default")
      (node (ref "U2") (pin "VIN") (pinfunction "VIN_VIN") (pintype "bidirectional"))
    )
    (net (code "117") (name "unconnected-(USB-ID-Pad4)") (class "Default")
      (node (ref "USB") (pin "4") (pinfunction "ID_4") (pintype "bidirectional"))
    )
  )
)
